# Power.net
KiCad netlist of a schematic drawn in EAGLE
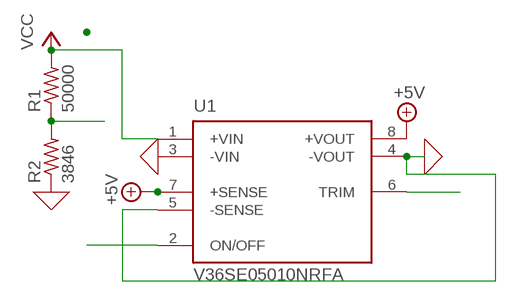
[diagram p0: schematic, sheet 1]

(export (version "E")
  (design (tool "Eeschema 10.0.6"))
  (components
    (comp (ref "R1")
      (value "50000")
      (footprint "eagle-import:0204_7")
      (libsource (lib "eagle-import") (part "R-US_0204/7"))
    )
    (comp (ref "R2")
      (value "3846")
      (footprint "eagle-import:0204_7")
      (libsource (lib "eagle-import") (part "R-US_0204/7"))
    )
    (comp (ref "U1")
      (value "V36SE05010NRFA")
      (footprint "eagle-import:MODULE_V36SE05010NRFA")
      (fields (field (name "MANUFACTURER") "Delta Electronics"))
      (libsource (lib "eagle-import") (part "V36SE05010NRFA"))
    )
  )
  (nets
    (net (code "1") (name "+5V") (class "Default")
      (node (ref "U1") (pin "7") (pinfunction "+SENSE_7") (pintype "input"))
      (node (ref "U1") (pin "8") (pinfunction "+VOUT_8") (pintype "output"))
    )
    (net (code "2") (name "GND") (class "Default")
      (node (ref "R2") (pin "1") (pinfunction "1_1") (pintype "passive"))
      (node (ref "U1") (pin "3") (pinfunction "-VIN_3") (pintype "input"))
      (node (ref "U1") (pin "4") (pinfunction "-VOUT_4") (pintype "output"))
      (node (ref "U1") (pin "5") (pinfunction "-SENSE_5") (pintype "input"))
    )
    (net (code "3") (name "Net-(R1-Pad1)") (class "Default")
      (node (ref "R1") (pin "1") (pinfunction "1_1") (pintype "passive"))
      (node (ref "R2") (pin "2") (pinfunction "2_2") (pintype "passive"))
    )
    (net (code "4") (name "VCC") (class "Default")
      (node (ref "R1") (pin "2") (pinfunction "2_2") (pintype "passive"))
      (node (ref "U1") (pin "1") (pinfunction "+VIN_1") (pintype "input"))
    )
    (net (code "5") (name "unconnected-(U1-ON{slash}OFF-Pad2)") (class "Default")
      (node (ref "U1") (pin "2") (pinfunction "ON/OFF_2") (pintype "input"))
    )
    (net (code "6") (name "unconnected-(U1-TRIM-Pad6)") (class "Default")
      (node (ref "U1") (pin "6") (pinfunction "TRIM_6") (pintype "bidirectional"))
    )
  )
)
